# h-bridge.net
KiCad netlist of a schematic drawn in EAGLE
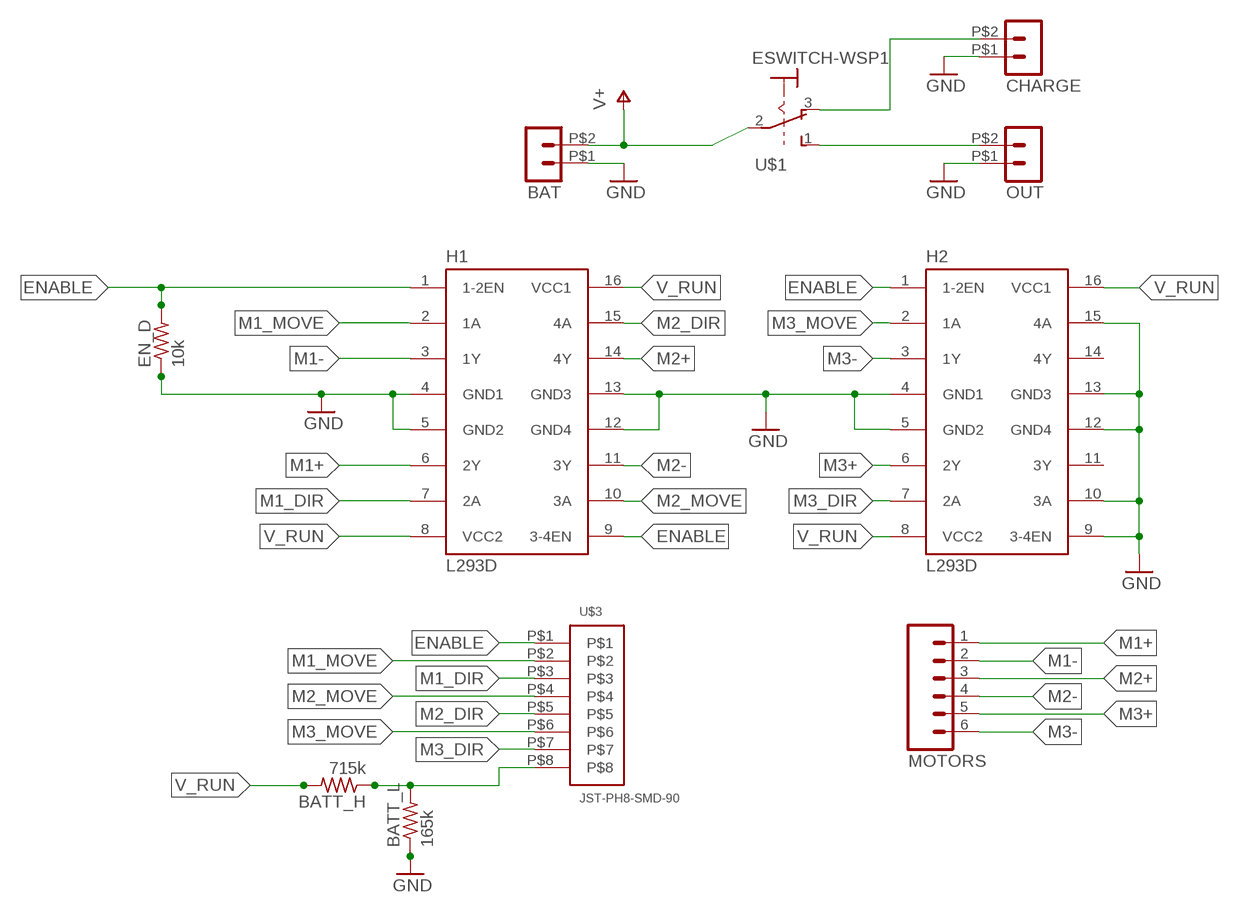
[diagram p0: schematic, sheet 1]

(export (version "E")
  (design (tool "Eeschema 10.0.6"))
  (components
    (comp (ref "BAT")
      (value "HEADER_POS2_43045-0206")
      (footprint "eagle-import:43045-0206")
      (libsource (lib "eagle-import") (part "HEADER_POS2_?43045-0206"))
    )
    (comp (ref "BATT_H")
      (value "715k")
      (footprint "eagle-import:R0805")
      (libsource (lib "eagle-import") (part "R-US_R0805"))
    )
    (comp (ref "BATT_L")
      (value "165k")
      (footprint "eagle-import:R0805")
      (libsource (lib "eagle-import") (part "R-US_R0805"))
    )
    (comp (ref "CHARGE")
      (value "HEADER_POS2_43045-0206")
      (footprint "eagle-import:43045-0206")
      (libsource (lib "eagle-import") (part "HEADER_POS2_?43045-0206"))
    )
    (comp (ref "EN_D")
      (value "10k")
      (footprint "eagle-import:R0805")
      (libsource (lib "eagle-import") (part "R-US_R0805"))
    )
    (comp (ref "H1")
      (value "L293D")
      (footprint "eagle-import:DIL16")
      (libsource (lib "eagle-import") (part "L293D"))
    )
    (comp (ref "H2")
      (value "L293D")
      (footprint "eagle-import:DIL16")
      (libsource (lib "eagle-import") (part "L293D"))
    )
    (comp (ref "MOTORS")
      (value "M06LOCK")
      (footprint "eagle-import:1X06_LOCK")
      (libsource (lib "eagle-import") (part "M06LOCK"))
    )
    (comp (ref "OUT")
      (value "HEADER_POS2_43045-0206")
      (footprint "eagle-import:43045-0206")
      (libsource (lib "eagle-import") (part "HEADER_POS2_?43045-0206"))
    )
    (comp (ref "U$1")
      (value "ESWITCH-WSP1")
      (footprint "eagle-import:WSP1-T2-M6")
      (libsource (lib "eagle-import") (part "ESWITCH-WSP1"))
    )
    (comp (ref "U$3")
      (value "JST-PH8-SMD-90")
      (footprint "eagle-import:JST-PH-SMD-90_")
      (libsource (lib "eagle-import") (part "JST-PH8-SMD-90"))
    )
  )
  (nets
    (net (code "1") (name "ENABLE") (class "Default")
      (node (ref "EN_D") (pin "2") (pinfunction "2_2") (pintype "passive"))
      (node (ref "H1") (pin "1") (pinfunction "1-2EN_1") (pintype "input"))
      (node (ref "H1") (pin "9") (pinfunction "3-4EN_9") (pintype "input"))
      (node (ref "H2") (pin "1") (pinfunction "1-2EN_1") (pintype "input"))
      (node (ref "U$3") (pin "P$1") (pinfunction "P$1_P$1") (pintype "bidirectional"))
    )
    (net (code "2") (name "GND") (class "Default")
      (node (ref "BAT") (pin "P$1") (pinfunction "1_P$1") (pintype "passive"))
      (node (ref "BATT_L") (pin "1") (pinfunction "1_1") (pintype "passive"))
      (node (ref "CHARGE") (pin "P$1") (pinfunction "1_P$1") (pintype "passive"))
      (node (ref "EN_D") (pin "1") (pinfunction "1_1") (pintype "passive"))
      (node (ref "H1") (pin "12") (pinfunction "GND4_12") (pintype "power_in"))
      (node (ref "H1") (pin "13") (pinfunction "GND3_13") (pintype "power_in"))
      (node (ref "H1") (pin "4") (pinfunction "GND1_4") (pintype "power_in"))
      (node (ref "H1") (pin "5") (pinfunction "GND2_5") (pintype "power_in"))
      (node (ref "H2") (pin "10") (pinfunction "3A_10") (pintype "input"))
      (node (ref "H2") (pin "12") (pinfunction "GND4_12") (pintype "power_in"))
      (node (ref "H2") (pin "13") (pinfunction "GND3_13") (pintype "power_in"))
      (node (ref "H2") (pin "15") (pinfunction "4A_15") (pintype "input"))
      (node (ref "H2") (pin "4") (pinfunction "GND1_4") (pintype "power_in"))
      (node (ref "H2") (pin "5") (pinfunction "GND2_5") (pintype "power_in"))
      (node (ref "H2") (pin "9") (pinfunction "3-4EN_9") (pintype "input"))
      (node (ref "OUT") (pin "P$1") (pinfunction "1_P$1") (pintype "passive"))
    )
    (net (code "3") (name "M1+") (class "Default")
      (node (ref "H1") (pin "6") (pinfunction "2Y_6") (pintype "output"))
      (node (ref "MOTORS") (pin "1") (pinfunction "1_1") (pintype "passive"))
    )
    (net (code "4") (name "M1-") (class "Default")
      (node (ref "H1") (pin "3") (pinfunction "1Y_3") (pintype "output"))
      (node (ref "MOTORS") (pin "2") (pinfunction "2_2") (pintype "passive"))
    )
    (net (code "5") (name "M1_DIR") (class "Default")
      (node (ref "H1") (pin "7") (pinfunction "2A_7") (pintype "input"))
      (node (ref "U$3") (pin "P$3") (pinfunction "P$3_P$3") (pintype "bidirectional"))
    )
    (net (code "6") (name "M1_MOVE") (class "Default")
      (node (ref "H1") (pin "2") (pinfunction "1A_2") (pintype "input"))
      (node (ref "U$3") (pin "P$2") (pinfunction "P$2_P$2") (pintype "bidirectional"))
    )
    (net (code "7") (name "M2+") (class "Default")
      (node (ref "H1") (pin "14") (pinfunction "4Y_14") (pintype "output"))
      (node (ref "MOTORS") (pin "3") (pinfunction "3_3") (pintype "passive"))
    )
    (net (code "8") (name "M2-") (class "Default")
      (node (ref "H1") (pin "11") (pinfunction "3Y_11") (pintype "output"))
      (node (ref "MOTORS") (pin "4") (pinfunction "4_4") (pintype "passive"))
    )
    (net (code "9") (name "M2_DIR") (class "Default")
      (node (ref "H1") (pin "15") (pinfunction "4A_15") (pintype "input"))
      (node (ref "U$3") (pin "P$5") (pinfunction "P$5_P$5") (pintype "bidirectional"))
    )
    (net (code "10") (name "M2_MOVE") (class "Default")
      (node (ref "H1") (pin "10") (pinfunction "3A_10") (pintype "input"))
      (node (ref "U$3") (pin "P$4") (pinfunction "P$4_P$4") (pintype "bidirectional"))
    )
    (net (code "11") (name "M3+") (class "Default")
      (node (ref "H2") (pin "6") (pinfunction "2Y_6") (pintype "output"))
      (node (ref "MOTORS") (pin "5") (pinfunction "5_5") (pintype "passive"))
    )
    (net (code "12") (name "M3-") (class "Default")
      (node (ref "H2") (pin "3") (pinfunction "1Y_3") (pintype "output"))
      (node (ref "MOTORS") (pin "6") (pinfunction "6_6") (pintype "passive"))
    )
    (net (code "13") (name "M3_DIR") (class "Default")
      (node (ref "H2") (pin "7") (pinfunction "2A_7") (pintype "input"))
      (node (ref "U$3") (pin "P$7") (pinfunction "P$7_P$7") (pintype "bidirectional"))
    )
    (net (code "14") (name "M3_MOVE") (class "Default")
      (node (ref "H2") (pin "2") (pinfunction "1A_2") (pintype "input"))
      (node (ref "U$3") (pin "P$6") (pinfunction "P$6_P$6") (pintype "bidirectional"))
    )
    (net (code "15") (name "Net-(BATT_H-Pad1)") (class "Default")
      (node (ref "BATT_H") (pin "1") (pinfunction "1_1") (pintype "passive"))
      (node (ref "BATT_L") (pin "2") (pinfunction "2_2") (pintype "passive"))
      (node (ref "U$3") (pin "P$8") (pinfunction "P$8_P$8") (pintype "bidirectional"))
    )
    (net (code "16") (name "Net-(CHARGE-2)") (class "Default")
      (node (ref "CHARGE") (pin "P$2") (pinfunction "2_P$2") (pintype "passive"))
      (node (ref "U$1") (pin "3") (pinfunction "3_3") (pintype "passive"))
    )
    (net (code "17") (name "V+") (class "Default")
      (node (ref "BAT") (pin "P$2") (pinfunction "2_P$2") (pintype "passive"))
      (node (ref "U$1") (pin "2") (pinfunction "2_2") (pintype "passive"))
    )
    (net (code "18") (name "V_RUN") (class "Default")
      (node (ref "BATT_H") (pin "2") (pinfunction "2_2") (pintype "passive"))
      (node (ref "H1") (pin "16") (pinfunction "VCC1_16") (pintype "power_in"))
      (node (ref "H1") (pin "8") (pinfunction "VCC2_8") (pintype "power_in"))
      (node (ref "H2") (pin "16") (pinfunction "VCC1_16") (pintype "power_in"))
      (node (ref "H2") (pin "8") (pinfunction "VCC2_8") (pintype "power_in"))
      (node (ref "OUT") (pin "P$2") (pinfunction "2_P$2") (pintype "passive"))
      (node (ref "U$1") (pin "1") (pinfunction "1_1") (pintype "passive"))
    )
    (net (code "19") (name "unconnected-(H2-3Y-Pad11)") (class "Default")
      (node (ref "H2") (pin "11") (pinfunction "3Y_11") (pintype "output"))
    )
    (net (code "20") (name "unconnected-(H2-4Y-Pad14)") (class "Default")
      (node (ref "H2") (pin "14") (pinfunction "4Y_14") (pintype "output"))
    )
  )
)
